# SimpleNode3.net
KiCad netlist of a schematic drawn in Altium Designer
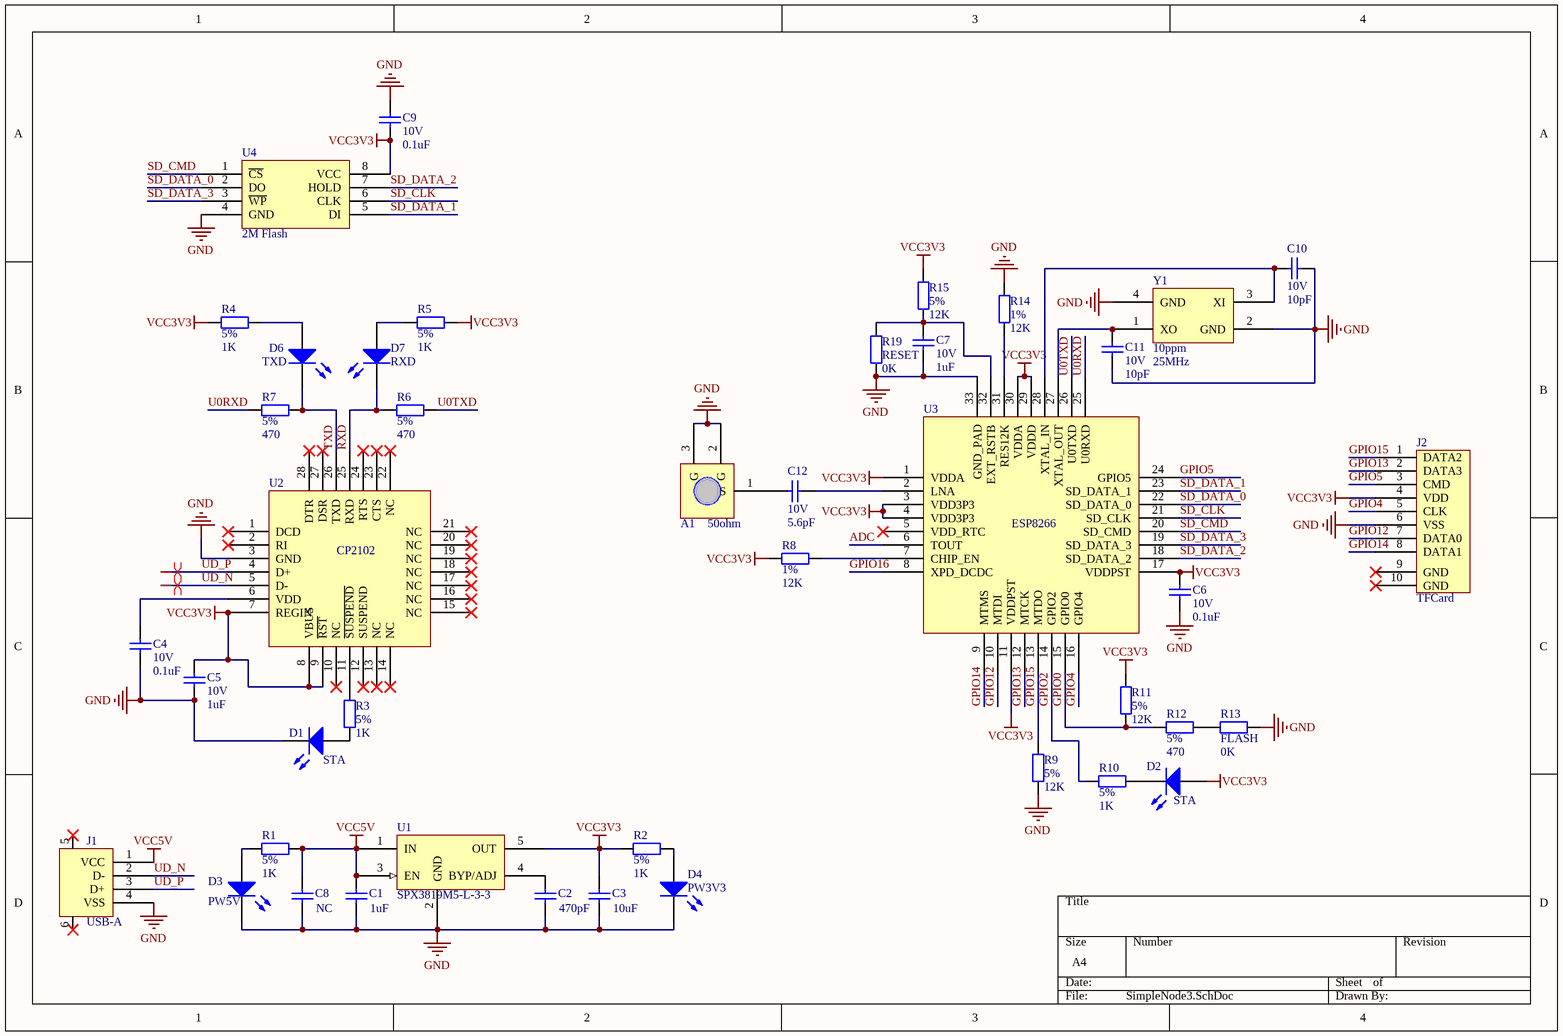
[diagram p0: SimpleNode3.SchDoc]

(export (version "E")
  (design (tool "Eeschema 10.0.6"))
  (components
    (comp (ref "A1")
      (value "50ohm")
      (footprint "IPEX-1 底座")
      (description "IPEX-1 底座")
      (libsource (lib "基础连接件") (part "IPEX-1 底座"))
    )
    (comp (ref "C1")
      (value "1uF")
      (footprint "C0402")
      (description "贴片无极性电容")
      (fields (field (name "Comment") "105"))
      (libsource (lib "基础元器件") (part "贴片无极性电容"))
    )
    (comp (ref "C2")
      (value "470pF")
      (footprint "C0402")
      (description "贴片无极性电容")
      (fields (field (name "Comment") "CAP"))
      (libsource (lib "基础元器件") (part "贴片无极性电容"))
    )
    (comp (ref "C3")
      (value "10uF")
      (footprint "C0402")
      (description "贴片无极性电容")
      (fields (field (name "Comment") "CAP"))
      (libsource (lib "基础元器件") (part "贴片无极性电容"))
    )
    (comp (ref "C4")
      (value "10V")
      (footprint "C0402")
      (description "贴片无极性电容")
      (fields (field (name "ALTIUM_VALUE") "0.1uF"))
      (libsource (lib "基础元器件") (part "贴片无极性电容"))
    )
    (comp (ref "C5")
      (value "10V")
      (footprint "C0402")
      (description "贴片无极性电容")
      (fields (field (name "ALTIUM_VALUE") "1uF"))
      (libsource (lib "基础元器件") (part "贴片无极性电容"))
    )
    (comp (ref "C6")
      (value "10V")
      (footprint "C0402")
      (description "贴片无极性电容")
      (fields (field (name "ALTIUM_VALUE") "0.1uF"))
      (libsource (lib "基础元器件") (part "贴片无极性电容"))
    )
    (comp (ref "C7")
      (value "10V")
      (footprint "C0402")
      (description "贴片无极性电容")
      (fields (field (name "ALTIUM_VALUE") "1uF"))
      (libsource (lib "基础元器件") (part "贴片无极性电容"))
    )
    (comp (ref "C8")
      (value "NC")
      (footprint "C0402")
      (description "贴片无极性电容")
      (fields (field (name "Comment") "CAP"))
      (libsource (lib "基础元器件") (part "贴片无极性电容"))
    )
    (comp (ref "C9")
      (value "10V")
      (footprint "C0402")
      (description "贴片无极性电容")
      (fields (field (name "ALTIUM_VALUE") "0.1uF"))
      (libsource (lib "基础元器件") (part "贴片无极性电容"))
    )
    (comp (ref "C10")
      (value "10V")
      (footprint "C0402")
      (description "贴片无极性电容")
      (fields (field (name "ALTIUM_VALUE") "10pF"))
      (libsource (lib "基础元器件") (part "贴片无极性电容"))
    )
    (comp (ref "C11")
      (value "10V")
      (footprint "C0402")
      (description "贴片无极性电容")
      (fields (field (name "ALTIUM_VALUE") "10pF"))
      (libsource (lib "基础元器件") (part "贴片无极性电容"))
    )
    (comp (ref "C12")
      (value "10V")
      (footprint "C0402")
      (description "贴片无极性电容")
      (fields (field (name "ALTIUM_VALUE") "5.6pF"))
      (libsource (lib "基础元器件") (part "贴片无极性电容"))
    )
    (comp (ref "D1")
      (value "STA")
      (footprint "LED0402")
      (description "贴片发光二级管")
      (libsource (lib "基础元器件") (part "贴片发光二级管"))
    )
    (comp (ref "D2")
      (value "STA")
      (footprint "LED0402")
      (description "贴片发光二级管")
      (libsource (lib "基础元器件") (part "贴片发光二级管"))
    )
    (comp (ref "D3")
      (value "PW5V")
      (footprint "LED0402")
      (description "贴片发光二级管")
      (libsource (lib "基础元器件") (part "贴片发光二级管"))
    )
    (comp (ref "D4")
      (value "PW3V3")
      (footprint "LED0402")
      (description "贴片发光二级管")
      (libsource (lib "基础元器件") (part "贴片发光二级管"))
    )
    (comp (ref "D6")
      (value "TXD")
      (footprint "LED0402")
      (description "贴片发光二级管")
      (libsource (lib "基础元器件") (part "贴片发光二级管"))
    )
    (comp (ref "D7")
      (value "RXD")
      (footprint "LED0402")
      (description "贴片发光二级管")
      (libsource (lib "基础元器件") (part "贴片发光二级管"))
    )
    (comp (ref "J1")
      (value "USB-A")
      (footprint "USB-A 公头")
      (description "USB-A 公头")
      (libsource (lib "基础连接件") (part "USB-A 公头"))
    )
    (comp (ref "J2")
      (value "TFCard")
      (footprint "TFCard 卡座 简易")
      (description "TFCard 卡座 简易")
      (libsource (lib "基础连接件") (part "TFCard 卡座 简易"))
    )
    (comp (ref "R1")
      (value "5%")
      (footprint "R0402")
      (description "贴片电阻")
      (fields (field (name "ALTIUM_VALUE") "1K"))
      (libsource (lib "") (part "贴片电阻_1"))
    )
    (comp (ref "R2")
      (value "5%")
      (footprint "R0402")
      (description "贴片电阻")
      (fields (field (name "ALTIUM_VALUE") "1K"))
      (libsource (lib "") (part "贴片电阻_1"))
    )
    (comp (ref "R3")
      (value "5%")
      (footprint "R0402")
      (description "贴片电阻")
      (fields (field (name "ALTIUM_VALUE") "1K"))
      (libsource (lib "基础元器件") (part "贴片电阻"))
    )
    (comp (ref "R4")
      (value "5%")
      (footprint "R0402")
      (description "贴片电阻")
      (fields (field (name "ALTIUM_VALUE") "1K"))
      (libsource (lib "") (part "贴片电阻_2"))
    )
    (comp (ref "R5")
      (value "5%")
      (footprint "R0402")
      (description "贴片电阻")
      (fields (field (name "ALTIUM_VALUE") "1K"))
      (libsource (lib "") (part "贴片电阻_2"))
    )
    (comp (ref "R6")
      (value "5%")
      (footprint "R0402")
      (description "贴片电阻")
      (fields (field (name "ALTIUM_VALUE") "470"))
      (libsource (lib "") (part "贴片电阻_1"))
    )
    (comp (ref "R7")
      (value "5%")
      (footprint "R0402")
      (description "贴片电阻")
      (fields (field (name "ALTIUM_VALUE") "470"))
      (libsource (lib "") (part "贴片电阻_1"))
    )
    (comp (ref "R8")
      (value "1%")
      (footprint "R0402")
      (description "贴片电阻")
      (fields (field (name "ALTIUM_VALUE") "12K"))
      (libsource (lib "") (part "贴片电阻_2"))
    )
    (comp (ref "R9")
      (value "5%")
      (footprint "R0402")
      (description "贴片电阻")
      (fields (field (name "ALTIUM_VALUE") "12K"))
      (libsource (lib "基础元器件") (part "贴片电阻"))
    )
    (comp (ref "R10")
      (value "5%")
      (footprint "R0402")
      (description "贴片电阻")
      (fields (field (name "ALTIUM_VALUE") "1K"))
      (libsource (lib "") (part "贴片电阻_1"))
    )
    (comp (ref "R11")
      (value "5%")
      (footprint "R0402")
      (description "贴片电阻")
      (fields (field (name "ALTIUM_VALUE") "12K"))
      (libsource (lib "基础元器件") (part "贴片电阻"))
    )
    (comp (ref "R12")
      (value "5%")
      (footprint "R0402")
      (description "贴片电阻")
      (fields (field (name "ALTIUM_VALUE") "470"))
      (libsource (lib "") (part "贴片电阻_2"))
    )
    (comp (ref "R13")
      (value "FLASH")
      (footprint "R0402")
      (description "贴片电阻")
      (fields (field (name "ALTIUM_VALUE") "0K"))
      (libsource (lib "") (part "贴片电阻_1"))
    )
    (comp (ref "R14")
      (value "1%")
      (footprint "R0402")
      (description "贴片电阻")
      (fields (field (name "ALTIUM_VALUE") "12K"))
      (libsource (lib "基础元器件") (part "贴片电阻"))
    )
    (comp (ref "R15")
      (value "5%")
      (footprint "R0402")
      (description "贴片电阻")
      (fields (field (name "ALTIUM_VALUE") "12K"))
      (libsource (lib "基础元器件") (part "贴片电阻"))
    )
    (comp (ref "R19")
      (value "RESET")
      (footprint "R0402")
      (description "贴片电阻")
      (fields (field (name "ALTIUM_VALUE") "0K"))
      (libsource (lib "基础元器件") (part "贴片电阻"))
    )
    (comp (ref "U1")
      (value "SPX3819M5-L-3-3")
      (footprint "SOT25-5")
      (description "贴片5V转3.3V芯片")
      (libsource (lib "基础元器件") (part "SPX3819M5-L-3-3"))
    )
    (comp (ref "U2")
      (value "CP2102")
      (footprint "MLP28")
      (description "贴片USB转TTL")
      (libsource (lib "基础元器件") (part "CP2102"))
    )
    (comp (ref "U3")
      (value "ESP8266")
      (footprint "QFN32L")
      (description "ESP8266无线WiFi芯片")
      (libsource (lib "基础元器件") (part "ESP8266"))
    )
    (comp (ref "U4")
      (value "2M Flash")
      (footprint "SOIC8")
      (description "贴片2M存储Flash芯片")
      (libsource (lib "基础元器件") (part "GD25Q16CSIG"))
    )
    (comp (ref "Y1")
      (value "10ppm")
      (footprint "XTAL-2520")
      (description "贴片无源晶振")
      (fields (field (name "ALTIUM_VALUE") "25MHz"))
      (libsource (lib "基础元器件") (part "贴片无源晶振"))
    )
  )
  (nets
    (net (code "1") (name "/ADC") (class "Default")
      (node (ref "U3") (pin "6") (pinfunction "TOUT_6") (pintype "passive"))
    )
    (net (code "2") (name "/GPIO0") (class "Default")
      (node (ref "R11") (pin "1") (pinfunction "1_1") (pintype "passive"))
      (node (ref "R12") (pin "1") (pinfunction "1_1") (pintype "passive"))
      (node (ref "U3") (pin "15") (pinfunction "GPIO0_15") (pintype "passive"))
    )
    (net (code "3") (name "/GPIO2") (class "Default")
      (node (ref "R10") (pin "2") (pinfunction "2_2") (pintype "passive"))
      (node (ref "U3") (pin "14") (pinfunction "GPIO2_14") (pintype "passive"))
    )
    (net (code "4") (name "/GPIO4") (class "Default")
      (node (ref "J2") (pin "5") (pinfunction "CLK_5") (pintype "passive"))
      (node (ref "U3") (pin "16") (pinfunction "GPIO4_16") (pintype "passive"))
    )
    (net (code "5") (name "/GPIO5") (class "Default")
      (node (ref "J2") (pin "3") (pinfunction "CMD_3") (pintype "passive"))
      (node (ref "U3") (pin "24") (pinfunction "GPIO5_24") (pintype "passive"))
    )
    (net (code "6") (name "/GPIO12") (class "Default")
      (node (ref "J2") (pin "7") (pinfunction "DATA0_7") (pintype "passive"))
      (node (ref "U3") (pin "10") (pinfunction "MTDI_10") (pintype "passive"))
    )
    (net (code "7") (name "/GPIO13") (class "Default")
      (node (ref "J2") (pin "2") (pinfunction "DATA3_2") (pintype "passive"))
      (node (ref "U3") (pin "12") (pinfunction "MTCK_12") (pintype "passive"))
    )
    (net (code "8") (name "/GPIO14") (class "Default")
      (node (ref "J2") (pin "8") (pinfunction "DATA1_8") (pintype "passive"))
      (node (ref "U3") (pin "9") (pinfunction "MTMS_9") (pintype "passive"))
    )
    (net (code "9") (name "/GPIO15") (class "Default")
      (node (ref "J2") (pin "1") (pinfunction "DATA2_1") (pintype "passive"))
      (node (ref "R9") (pin "2") (pinfunction "2_2") (pintype "passive"))
      (node (ref "U3") (pin "13") (pinfunction "MTDO_13") (pintype "passive"))
    )
    (net (code "10") (name "/GPIO16") (class "Default")
      (node (ref "U3") (pin "8") (pinfunction "XPD_DCDC_8") (pintype "passive"))
    )
    (net (code "11") (name "/RXD") (class "Default")
      (node (ref "D7") (pin "2") (pinfunction "K_2") (pintype "passive"))
      (node (ref "R6") (pin "2") (pinfunction "2_2") (pintype "passive"))
      (node (ref "U2") (pin "25") (pinfunction "RXD_25") (pintype "passive"))
    )
    (net (code "12") (name "/SD_CLK") (class "Default")
      (node (ref "U3") (pin "21") (pinfunction "SD_CLK_21") (pintype "passive"))
      (node (ref "U4") (pin "6") (pinfunction "CLK_6") (pintype "passive"))
    )
    (net (code "13") (name "/SD_CMD") (class "Default")
      (node (ref "U3") (pin "20") (pinfunction "SD_CMD_20") (pintype "passive"))
      (node (ref "U4") (pin "1") (pinfunction "~{CS}_1") (pintype "passive"))
    )
    (net (code "14") (name "/SD_DATA_0") (class "Default")
      (node (ref "U3") (pin "22") (pinfunction "SD_DATA_0_22") (pintype "passive"))
      (node (ref "U4") (pin "2") (pinfunction "DO_2") (pintype "passive"))
    )
    (net (code "15") (name "/SD_DATA_1") (class "Default")
      (node (ref "U3") (pin "23") (pinfunction "SD_DATA_1_23") (pintype "passive"))
      (node (ref "U4") (pin "5") (pinfunction "DI_5") (pintype "passive"))
    )
    (net (code "16") (name "/SD_DATA_2") (class "Default")
      (node (ref "U3") (pin "18") (pinfunction "SD_DATA_2_18") (pintype "passive"))
      (node (ref "U4") (pin "7") (pinfunction "HOLD_7") (pintype "passive"))
    )
    (net (code "17") (name "/SD_DATA_3") (class "Default")
      (node (ref "U3") (pin "19") (pinfunction "SD_DATA_3_19") (pintype "passive"))
      (node (ref "U4") (pin "3") (pinfunction "~{WP}_3") (pintype "passive"))
    )
    (net (code "18") (name "/TXD") (class "Default")
      (node (ref "D6") (pin "2") (pinfunction "K_2") (pintype "passive"))
      (node (ref "R7") (pin "1") (pinfunction "1_1") (pintype "passive"))
      (node (ref "U2") (pin "26") (pinfunction "TXD_26") (pintype "passive"))
    )
    (net (code "19") (name "/U0RXD") (class "Default")
      (node (ref "R7") (pin "2") (pinfunction "2_2") (pintype "passive"))
      (node (ref "U3") (pin "25") (pinfunction "U0RXD_25") (pintype "passive"))
    )
    (net (code "20") (name "/U0TXD") (class "Default")
      (node (ref "R6") (pin "1") (pinfunction "1_1") (pintype "passive"))
      (node (ref "U3") (pin "26") (pinfunction "U0TXD_26") (pintype "passive"))
    )
    (net (code "21") (name "/UD_N") (class "Default")
      (node (ref "J1") (pin "2") (pinfunction "D-_2") (pintype "passive"))
      (node (ref "U2") (pin "5") (pinfunction "D-_5") (pintype "passive"))
    )
    (net (code "22") (name "/UD_P") (class "Default")
      (node (ref "J1") (pin "3") (pinfunction "D+_3") (pintype "passive"))
      (node (ref "U2") (pin "4") (pinfunction "D+_4") (pintype "passive"))
    )
    (net (code "23") (name "GND") (class "Default")
      (node (ref "A1") (pin "2") (pinfunction "G_2") (pintype "passive"))
      (node (ref "A1") (pin "3") (pinfunction "G_3") (pintype "passive"))
      (node (ref "C1") (pin "1") (pinfunction "1_1") (pintype "passive"))
      (node (ref "C10") (pin "2") (pinfunction "2_2") (pintype "passive"))
      (node (ref "C11") (pin "2") (pinfunction "2_2") (pintype "passive"))
      (node (ref "C2") (pin "1") (pinfunction "1_1") (pintype "passive"))
      (node (ref "C3") (pin "1") (pinfunction "1_1") (pintype "passive"))
      (node (ref "C4") (pin "1") (pinfunction "1_1") (pintype "passive"))
      (node (ref "C5") (pin "1") (pinfunction "1_1") (pintype "passive"))
      (node (ref "C6") (pin "1") (pinfunction "1_1") (pintype "passive"))
      (node (ref "C7") (pin "1") (pinfunction "1_1") (pintype "passive"))
      (node (ref "C8") (pin "1") (pinfunction "1_1") (pintype "passive"))
      (node (ref "C9") (pin "1") (pinfunction "1_1") (pintype "passive"))
      (node (ref "D1") (pin "2") (pinfunction "K_2") (pintype "passive"))
      (node (ref "D3") (pin "2") (pinfunction "K_2") (pintype "passive"))
      (node (ref "D4") (pin "2") (pinfunction "K_2") (pintype "passive"))
      (node (ref "J1") (pin "4") (pinfunction "VSS_4") (pintype "passive"))
      (node (ref "J2") (pin "6") (pinfunction "VSS_6") (pintype "passive"))
      (node (ref "R13") (pin "1") (pinfunction "1_1") (pintype "passive"))
      (node (ref "R14") (pin "2") (pinfunction "2_2") (pintype "passive"))
      (node (ref "R19") (pin "1") (pinfunction "1_1") (pintype "passive"))
      (node (ref "R9") (pin "1") (pinfunction "1_1") (pintype "passive"))
      (node (ref "U1") (pin "2") (pinfunction "GND_2") (pintype "power_in"))
      (node (ref "U2") (pin "3") (pinfunction "GND_3") (pintype "passive"))
      (node (ref "U3") (pin "33") (pinfunction "GND_PAD_33") (pintype "passive"))
      (node (ref "U4") (pin "4") (pinfunction "GND_4") (pintype "passive"))
      (node (ref "Y1") (pin "2") (pinfunction "GND_2") (pintype "passive"))
      (node (ref "Y1") (pin "4") (pinfunction "GND_4") (pintype "passive"))
    )
    (net (code "24") (name "Net-(A1-S)") (class "Default")
      (node (ref "A1") (pin "1") (pinfunction "S_1") (pintype "passive"))
      (node (ref "C12") (pin "1") (pinfunction "1_1") (pintype "passive"))
    )
    (net (code "25") (name "Net-(D1-A)") (class "Default")
      (node (ref "D1") (pin "1") (pinfunction "A_1") (pintype "passive"))
      (node (ref "R3") (pin "1") (pinfunction "1_1") (pintype "passive"))
    )
    (net (code "26") (name "Net-(D2-K)") (class "Default")
      (node (ref "D2") (pin "2") (pinfunction "K_2") (pintype "passive"))
      (node (ref "R10") (pin "1") (pinfunction "1_1") (pintype "passive"))
    )
    (net (code "27") (name "Net-(D3-A)") (class "Default")
      (node (ref "D3") (pin "1") (pinfunction "A_1") (pintype "passive"))
      (node (ref "R1") (pin "2") (pinfunction "2_2") (pintype "passive"))
    )
    (net (code "28") (name "Net-(D4-A)") (class "Default")
      (node (ref "D4") (pin "1") (pinfunction "A_1") (pintype "passive"))
      (node (ref "R2") (pin "1") (pinfunction "1_1") (pintype "passive"))
    )
    (net (code "29") (name "Net-(D6-A)") (class "Default")
      (node (ref "D6") (pin "1") (pinfunction "A_1") (pintype "passive"))
      (node (ref "R4") (pin "2") (pinfunction "2_2") (pintype "passive"))
    )
    (net (code "30") (name "Net-(D7-A)") (class "Default")
      (node (ref "D7") (pin "1") (pinfunction "A_1") (pintype "passive"))
      (node (ref "R5") (pin "1") (pinfunction "1_1") (pintype "passive"))
    )
    (net (code "31") (name "Net-(R12-Pad2)") (class "Default")
      (node (ref "R12") (pin "2") (pinfunction "2_2") (pintype "passive"))
      (node (ref "R13") (pin "2") (pinfunction "2_2") (pintype "passive"))
    )
    (net (code "32") (name "Net-(U1-BYP{slash}ADJ)") (class "Default")
      (node (ref "C2") (pin "2") (pinfunction "2_2") (pintype "passive"))
      (node (ref "U1") (pin "4") (pinfunction "BYP/ADJ_4") (pintype "passive"))
    )
    (net (code "33") (name "Net-(U2-VDD)") (class "Default")
      (node (ref "C4") (pin "2") (pinfunction "2_2") (pintype "passive"))
      (node (ref "U2") (pin "6") (pinfunction "VDD_6") (pintype "passive"))
    )
    (net (code "34") (name "Net-(U2-~{SUSPEND})") (class "Default")
      (node (ref "R3") (pin "2") (pinfunction "2_2") (pintype "passive"))
      (node (ref "U2") (pin "11") (pinfunction "~{SUSPEND}_11") (pintype "passive"))
    )
    (net (code "35") (name "Net-(U3-CHIP_EN)") (class "Default")
      (node (ref "R8") (pin "2") (pinfunction "2_2") (pintype "passive"))
      (node (ref "U3") (pin "7") (pinfunction "CHIP_EN_7") (pintype "passive"))
    )
    (net (code "36") (name "Net-(U3-EXT_RSTB)") (class "Default")
      (node (ref "C7") (pin "2") (pinfunction "2_2") (pintype "passive"))
      (node (ref "R15") (pin "1") (pinfunction "1_1") (pintype "passive"))
      (node (ref "R19") (pin "2") (pinfunction "2_2") (pintype "passive"))
      (node (ref "U3") (pin "32") (pinfunction "EXT_RSTB_32") (pintype "passive"))
    )
    (net (code "37") (name "Net-(U3-LNA)") (class "Default")
      (node (ref "C12") (pin "2") (pinfunction "2_2") (pintype "passive"))
      (node (ref "U3") (pin "2") (pinfunction "LNA_2") (pintype "passive"))
    )
    (net (code "38") (name "Net-(U3-RES12K)") (class "Default")
      (node (ref "R14") (pin "1") (pinfunction "1_1") (pintype "passive"))
      (node (ref "U3") (pin "31") (pinfunction "RES12K_31") (pintype "passive"))
    )
    (net (code "39") (name "Net-(U3-XTAL_IN)") (class "Default")
      (node (ref "C10") (pin "1") (pinfunction "1_1") (pintype "passive"))
      (node (ref "U3") (pin "28") (pinfunction "XTAL_IN_28") (pintype "passive"))
      (node (ref "Y1") (pin "3") (pinfunction "XI_3") (pintype "passive"))
    )
    (net (code "40") (name "Net-(U3-XTAL_OUT)") (class "Default")
      (node (ref "C11") (pin "1") (pinfunction "1_1") (pintype "passive"))
      (node (ref "U3") (pin "27") (pinfunction "XTAL_OUT_27") (pintype "passive"))
      (node (ref "Y1") (pin "1") (pinfunction "XO_1") (pintype "passive"))
    )
    (net (code "41") (name "VCC3V3") (class "Default")
      (node (ref "C3") (pin "2") (pinfunction "2_2") (pintype "passive"))
      (node (ref "C5") (pin "2") (pinfunction "2_2") (pintype "passive"))
      (node (ref "C6") (pin "2") (pinfunction "2_2") (pintype "passive"))
      (node (ref "C9") (pin "2") (pinfunction "2_2") (pintype "passive"))
      (node (ref "D2") (pin "1") (pinfunction "A_1") (pintype "passive"))
      (node (ref "J2") (pin "4") (pinfunction "VDD_4") (pintype "passive"))
      (node (ref "R11") (pin "2") (pinfunction "2_2") (pintype "passive"))
      (node (ref "R15") (pin "2") (pinfunction "2_2") (pintype "passive"))
      (node (ref "R2") (pin "2") (pinfunction "2_2") (pintype "passive"))
      (node (ref "R4") (pin "1") (pinfunction "1_1") (pintype "passive"))
      (node (ref "R5") (pin "2") (pinfunction "2_2") (pintype "passive"))
      (node (ref "R8") (pin "1") (pinfunction "1_1") (pintype "passive"))
      (node (ref "U1") (pin "5") (pinfunction "OUT_5") (pintype "power_in"))
      (node (ref "U2") (pin "7") (pinfunction "REGIN_7") (pintype "passive"))
      (node (ref "U2") (pin "8") (pinfunction "VBUS_8") (pintype "passive"))
      (node (ref "U2") (pin "9") (pinfunction "~{RST}_9") (pintype "passive"))
      (node (ref "U3") (pin "1") (pinfunction "VDDA_1") (pintype "passive"))
      (node (ref "U3") (pin "11") (pinfunction "VDDPST_11") (pintype "passive"))
      (node (ref "U3") (pin "17") (pinfunction "VDDPST_17") (pintype "passive"))
      (node (ref "U3") (pin "29") (pinfunction "VDDD_29") (pintype "passive"))
      (node (ref "U3") (pin "3") (pinfunction "VDD3P3_3") (pintype "passive"))
      (node (ref "U3") (pin "30") (pinfunction "VDDA_30") (pintype "passive"))
      (node (ref "U3") (pin "4") (pinfunction "VDD3P3_4") (pintype "passive"))
      (node (ref "U4") (pin "8") (pinfunction "VCC_8") (pintype "power_in"))
    )
    (net (code "42") (name "VCC5V") (class "Default")
      (node (ref "C1") (pin "2") (pinfunction "2_2") (pintype "passive"))
      (node (ref "C8") (pin "2") (pinfunction "2_2") (pintype "passive"))
      (node (ref "J1") (pin "1") (pinfunction "VCC_1") (pintype "passive"))
      (node (ref "R1") (pin "1") (pinfunction "1_1") (pintype "passive"))
      (node (ref "U1") (pin "1") (pinfunction "IN_1") (pintype "power_in"))
      (node (ref "U1") (pin "3") (pinfunction "EN_3") (pintype "input"))
    )
    (net (code "43") (name "unconnected-(J1-Pad5)") (class "Default")
      (node (ref "J1") (pin "5") (pinfunction "5_5") (pintype "passive+no_connect"))
    )
    (net (code "44") (name "unconnected-(J1-Pad6)") (class "Default")
      (node (ref "J1") (pin "6") (pinfunction "6_6") (pintype "passive+no_connect"))
    )
    (net (code "45") (name "unconnected-(J2-GND-Pad9)") (class "Default")
      (node (ref "J2") (pin "9") (pinfunction "GND_9") (pintype "passive+no_connect"))
    )
    (net (code "46") (name "unconnected-(J2-GND-Pad10)") (class "Default")
      (node (ref "J2") (pin "10") (pinfunction "GND_10") (pintype "passive+no_connect"))
    )
    (net (code "47") (name "unconnected-(U2-CTS-Pad23)") (class "Default")
      (node (ref "U2") (pin "23") (pinfunction "CTS_23") (pintype "passive+no_connect"))
    )
    (net (code "48") (name "unconnected-(U2-DCD-Pad1)") (class "Default")
      (node (ref "U2") (pin "1") (pinfunction "DCD_1") (pintype "passive+no_connect"))
    )
    (net (code "49") (name "unconnected-(U2-DSR-Pad27)") (class "Default")
      (node (ref "U2") (pin "27") (pinfunction "DSR_27") (pintype "passive+no_connect"))
    )
    (net (code "50") (name "unconnected-(U2-DTR-Pad28)") (class "Default")
      (node (ref "U2") (pin "28") (pinfunction "DTR_28") (pintype "passive+no_connect"))
    )
    (net (code "51") (name "unconnected-(U2-NC-Pad10)") (class "Default")
      (node (ref "U2") (pin "10") (pinfunction "NC_10") (pintype "passive+no_connect"))
    )
    (net (code "52") (name "unconnected-(U2-NC-Pad13)") (class "Default")
      (node (ref "U2") (pin "13") (pinfunction "NC_13") (pintype "passive+no_connect"))
    )
    (net (code "53") (name "unconnected-(U2-NC-Pad14)") (class "Default")
      (node (ref "U2") (pin "14") (pinfunction "NC_14") (pintype "passive+no_connect"))
    )
    (net (code "54") (name "unconnected-(U2-NC-Pad15)") (class "Default")
      (node (ref "U2") (pin "15") (pinfunction "NC_15") (pintype "passive+no_connect"))
    )
    (net (code "55") (name "unconnected-(U2-NC-Pad16)") (class "Default")
      (node (ref "U2") (pin "16") (pinfunction "NC_16") (pintype "passive+no_connect"))
    )
    (net (code "56") (name "unconnected-(U2-NC-Pad17)") (class "Default")
      (node (ref "U2") (pin "17") (pinfunction "NC_17") (pintype "passive+no_connect"))
    )
    (net (code "57") (name "unconnected-(U2-NC-Pad18)") (class "Default")
      (node (ref "U2") (pin "18") (pinfunction "NC_18") (pintype "passive+no_connect"))
    )
    (net (code "58") (name "unconnected-(U2-NC-Pad19)") (class "Default")
      (node (ref "U2") (pin "19") (pinfunction "NC_19") (pintype "passive+no_connect"))
    )
    (net (code "59") (name "unconnected-(U2-NC-Pad20)") (class "Default")
      (node (ref "U2") (pin "20") (pinfunction "NC_20") (pintype "passive+no_connect"))
    )
    (net (code "60") (name "unconnected-(U2-NC-Pad21)") (class "Default")
      (node (ref "U2") (pin "21") (pinfunction "NC_21") (pintype "passive+no_connect"))
    )
    (net (code "61") (name "unconnected-(U2-NC-Pad22)") (class "Default")
      (node (ref "U2") (pin "22") (pinfunction "NC_22") (pintype "passive+no_connect"))
    )
    (net (code "62") (name "unconnected-(U2-RI-Pad2)") (class "Default")
      (node (ref "U2") (pin "2") (pinfunction "RI_2") (pintype "passive+no_connect"))
    )
    (net (code "63") (name "unconnected-(U2-RTS-Pad24)") (class "Default")
      (node (ref "U2") (pin "24") (pinfunction "RTS_24") (pintype "passive+no_connect"))
    )
    (net (code "64") (name "unconnected-(U2-SUSPEND-Pad12)") (class "Default")
      (node (ref "U2") (pin "12") (pinfunction "SUSPEND_12") (pintype "passive+no_connect"))
    )
    (net (code "65") (name "unconnected-(U3-VDD_RTC-Pad5)") (class "Default")
      (node (ref "U3") (pin "5") (pinfunction "VDD_RTC_5") (pintype "passive+no_connect"))
    )
  )
)
